# Voltage_Source.net
KiCad netlist of a schematic drawn in Altium Designer
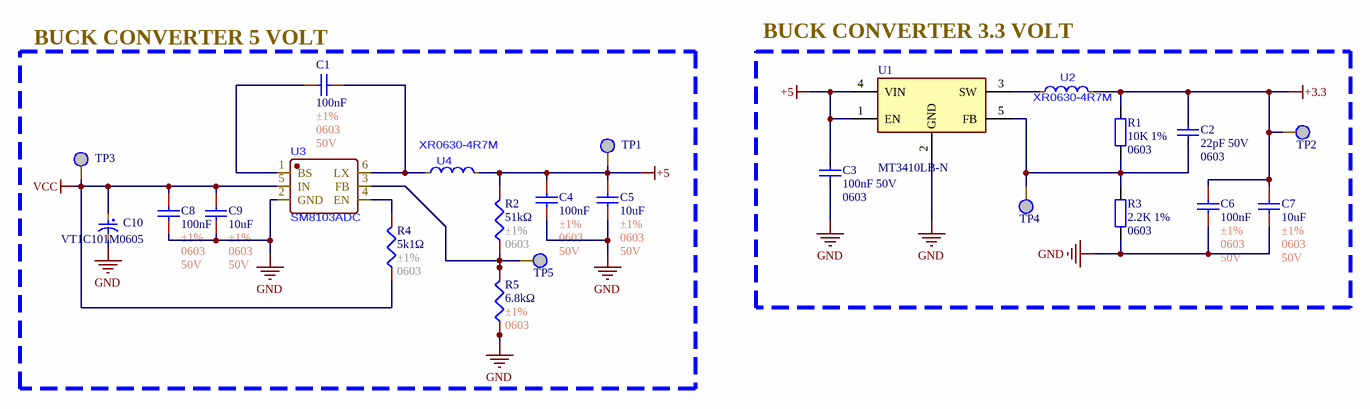
[diagram p0: Voltage Source.SchDoc]

(export (version "E")
  (design (tool "Eeschema 10.0.6"))
  (components
    (comp (ref "C1")
      (value "100nF")
      (footprint "C0603")
      (fields
        (field (name "MANUFACTURER") "YAGEO")
        (field (name "MFR. PART #") "CC0402FRNPO9BN100")
        (field (name "LCSC PART #") "C513681")
        (field (name "TOLERANCE") "±1%")
        (field (name "PACKAGE") "0603")
        (field (name "VOLTAGE RATING") "50V")
      )
      (libsource (lib "Capital") (part "C0603_100nF_±1%"))
    )
    (comp (ref "C2")
      (value "22pF 50V")
      (footprint "C0603")
      (description "50V 22pF NP0 ±5% 0603 Multilayer Ceramic Capacitors MLCC - SMD/SMT ROHS")
      (fields
        (field (name "MANUFACTURER") "YAGEO")
        (field (name "MANUFACTURE PART NUMBER") "CC0603JRNPO9BN220")
        (field (name "PACKAGE") "0603")
      )
      (libsource (lib "IOT SOLUTIONS LOAPAY V5.5.2") (part "C0603_MLCC_22pF_50V"))
    )
    (comp (ref "C3")
      (value "100nF 50V")
      (footprint "C0603")
      (description "50V 100nF X7R ±10% 0603 Multilayer Ceramic Capacitors MLCC - SMD/SMT ROHS")
      (fields
        (field (name "MANUFACTURER") "YAGEO")
        (field (name "MANUFACTURE PART NUMBER") "CC0603KRX7R9BB104")
        (field (name "PACKAGE") "0603")
      )
      (libsource (lib "IOT SOLUTIONS LOAPAY V5.5.2") (part "C0603_MLCC_100nF_50V"))
    )
    (comp (ref "C4")
      (value "100nF")
      (footprint "C0603")
      (fields
        (field (name "MANUFACTURER") "YAGEO")
        (field (name "MFR. PART #") "CC0402FRNPO9BN100")
        (field (name "LCSC PART #") "C513681")
        (field (name "TOLERANCE") "±1%")
        (field (name "PACKAGE") "0603")
        (field (name "VOLTAGE RATING") "50V")
      )
      (libsource (lib "Capital") (part "C0603_100nF_±1%"))
    )
    (comp (ref "C5")
      (value "10uF")
      (footprint "C0603")
      (fields
        (field (name "MANUFACTURER") "YAGEO")
        (field (name "MFR. PART #") "CC0402FRNPO9BN100")
        (field (name "LCSC PART #") "C513681")
        (field (name "TOLERANCE") "±1%")
        (field (name "PACKAGE") "0603")
        (field (name "VOLTAGE RATING") "50V")
      )
      (libsource (lib "Capital") (part "C0603_10uF_±1%"))
    )
    (comp (ref "C6")
      (value "100nF")
      (footprint "C0603")
      (fields
        (field (name "MANUFACTURER") "YAGEO")
        (field (name "MFR. PART #") "CC0402FRNPO9BN100")
        (field (name "LCSC PART #") "C513681")
        (field (name "TOLERANCE") "±1%")
        (field (name "PACKAGE") "0603")
        (field (name "VOLTAGE RATING") "50V")
      )
      (libsource (lib "Capital") (part "C0603_100nF_±1%"))
    )
    (comp (ref "C7")
      (value "10uF")
      (footprint "C0603")
      (fields
        (field (name "MANUFACTURER") "YAGEO")
        (field (name "MFR. PART #") "CC0402FRNPO9BN100")
        (field (name "LCSC PART #") "C513681")
        (field (name "TOLERANCE") "±1%")
        (field (name "PACKAGE") "0603")
        (field (name "VOLTAGE RATING") "50V")
      )
      (libsource (lib "Capital") (part "C0603_10uF_±1%"))
    )
    (comp (ref "C8")
      (value "100nF")
      (footprint "C0603")
      (fields
        (field (name "MANUFACTURER") "YAGEO")
        (field (name "MFR. PART #") "CC0402FRNPO9BN100")
        (field (name "LCSC PART #") "C513681")
        (field (name "TOLERANCE") "±1%")
        (field (name "PACKAGE") "0603")
        (field (name "VOLTAGE RATING") "50V")
      )
      (libsource (lib "Capital") (part "C0603_100nF_±1%"))
    )
    (comp (ref "C9")
      (value "10uF")
      (footprint "C0603")
      (fields
        (field (name "MANUFACTURER") "YAGEO")
        (field (name "MFR. PART #") "CC0402FRNPO9BN100")
        (field (name "LCSC PART #") "C513681")
        (field (name "TOLERANCE") "±1%")
        (field (name "PACKAGE") "0603")
        (field (name "VOLTAGE RATING") "50V")
      )
      (libsource (lib "Capital") (part "C0603_10uF_±1%"))
    )
    (comp (ref "C10")
      (value "VT1C101M0605")
      (footprint "C_100uF_16V_Aluminum")
      (description "100uF 16V ±20% 63mA@120Hz SMD,D6.3xL5.4mm Aluminum Electrolytic Capacitors RoHS")
      (fields (field (name "MANUFACTURER") "ROQANG") (field (name "LCSC PART #") "C90273"))
      (libsource (lib "Capital") (part "C_100uF_16V_aluminum"))
    )
    (comp (ref "R1")
      (value "10K 1%")
      (footprint "RES_SMD_0603")
      (description "10 kOhms ±1% 0.1W, 1/10W Chip Resistor 0603 (1608 Metric) Moisture Resistant Thick Film")
      (fields
        (field (name "MANUFACTURER") "YAGEO")
        (field (name "MANUFACTURE PART NUMBER") "RC0603FR-0710KL")
        (field (name "PACKAGE") "0603")
      )
      (libsource (lib "IOT SOLUTIONS LOAPAY V5.5.2") (part "R0603_10K"))
    )
    (comp (ref "R2")
      (value "51kΩ")
      (footprint "R0603")
      (description "100mW Thick Film Resistor 75V ±100ppm/℃ ±1% 51kΩ 0603 Chip Resistor - Surface Mount ROHS")
      (fields
        (field (name "MANUFACTURER") "FOJAN")
        (field (name "MFR. PART #") "FRC0603F5101TS")
        (field (name "TOLERANCE") "±1%")
        (field (name "PACKAGE") "0603")
      )
      (libsource (lib "Resistor") (part "R0603_51kΩ_±1%"))
    )
    (comp (ref "R3")
      (value "2.2K 1%")
      (footprint "RES_SMD_0603")
      (description "2.2 kOhms ±1% 0.1W, 1/10W Chip Resistor 0603 (1608 Metric) Moisture Resistant Thick Film")
      (fields
        (field (name "MANUFACTURER") "YAGEO")
        (field (name "MANUFACTURE PART NUMBER") "RC0603FR-072K2L")
        (field (name "PACKAGE") "0603")
      )
      (libsource (lib "IOT SOLUTIONS LOAPAY V5.5.2") (part "R0603_2.2K"))
    )
    (comp (ref "R4")
      (value "5k1Ω")
      (footprint "R0603")
      (description "100mW Thick Film Resistor 75V ±100ppm/℃ ±1% 5.1kΩ 0603 Chip Resistor - Surface Mount ROHS")
      (fields
        (field (name "MANUFACTURER") "FOJAN")
        (field (name "MFR. PART #") "FRC0603F5101TS")
        (field (name "TOLERANCE") "±1%")
        (field (name "PACKAGE") "0603")
      )
      (libsource (lib "Resistor") (part "R0603_5k1Ω_±1%"))
    )
    (comp (ref "R5")
      (value "6.8kΩ")
      (footprint "R0603")
      (description "6.8k")
      (fields
        (field (name "MANUFACTURER") "YAGEO")
        (field (name "MFR. PART #") "RC0402FR-0710RL")
        (field (name "TOLERANCE") "±1%")
        (field (name "PACKAGE") "0603")
      )
      (libsource (lib "Resistor") (part "R0603_6.8kΩ_±1%_1"))
    )
    (comp (ref "TP1") (value "TP") (footprint "TP") (libsource (lib "Other") (part "TP")))
    (comp (ref "TP2") (value "TP") (footprint "TP") (libsource (lib "Other") (part "TP")))
    (comp (ref "TP3") (value "TP") (footprint "TP") (libsource (lib "Other") (part "TP")))
    (comp (ref "TP4") (value "TP") (footprint "TP") (libsource (lib "Other") (part "TP")))
    (comp (ref "TP5") (value "TP") (footprint "TP") (libsource (lib "Other") (part "TP")))
    (comp (ref "U1")
      (value "MT3410LB-N")
      (footprint "SOT23_5")
      (description "SOT-23-5 DC-DC Converters ROHS")
      (fields (field (name "MANUFACTURER") "XI'AN Aerosemi Tech"))
      (libsource (lib "IOT SOLUTIONS LOAPAY V5.5.2") (part "MT3410LB-N"))
    )
    (comp (ref "U2")
      (value "XR0630-4R7M")
      (footprint "SMD,7x6.6mm")
      (description "FIXED IND 4.7uH 6A 33mΩ SMD,0630")
      (fields (field (name "MANUFACTURER") "XR") (field (name "LCSC PART #") "C5307631"))
      (libsource (lib "Inductor") (part "FIXED IND 4.7uH 6A 33mΩ SMD,0630"))
    )
    (comp (ref "U3")
      (value "SM8103ADC")
      (footprint "TSOT-23-6")
      (description "High Efficiency, 3.0A, 18V Input Synchronous Step Down Regulator")
      (fields (field (name "MANUFACTURER") "Silergy") (field (name "LCSC PART #") "C479070"))
      (libsource (lib "IC") (part "SM8103ADC"))
    )
    (comp (ref "U4")
      (value "XR0630-4R7M")
      (footprint "SMD,7x6.6mm")
      (description "FIXED IND 4.7uH 6A 33mΩ SMD,0630")
      (fields (field (name "MANUFACTURER") "XR") (field (name "LCSC PART #") "C5307631"))
      (libsource (lib "Inductor") (part "FIXED IND 4.7uH 6A 33mΩ SMD,0630"))
    )
  )
  (nets
    (net (code "1") (name "+3.3") (class "Default")
      (node (ref "C2") (pin "2") (pinfunction "2_2") (pintype "passive"))
      (node (ref "C6") (pin "1") (pinfunction "1_1") (pintype "passive"))
      (node (ref "C7") (pin "1") (pinfunction "1_1") (pintype "passive"))
      (node (ref "R1") (pin "2") (pinfunction "2_2") (pintype "passive"))
      (node (ref "TP2") (pin "1") (pinfunction "1_1") (pintype "passive"))
      (node (ref "U2") (pin "2") (pinfunction "F_2") (pintype "passive"))
    )
    (net (code "2") (name "+5") (class "Default")
      (node (ref "C3") (pin "2") (pinfunction "2_2") (pintype "passive"))
      (node (ref "C4") (pin "1") (pinfunction "1_1") (pintype "passive"))
      (node (ref "C5") (pin "1") (pinfunction "1_1") (pintype "passive"))
      (node (ref "R2") (pin "2") (pinfunction "2_2") (pintype "passive"))
      (node (ref "TP1") (pin "1") (pinfunction "1_1") (pintype "passive"))
      (node (ref "U1") (pin "1") (pinfunction "EN_1") (pintype "passive"))
      (node (ref "U1") (pin "4") (pinfunction "VIN_4") (pintype "passive"))
      (node (ref "U4") (pin "2") (pinfunction "F_2") (pintype "passive"))
    )
    (net (code "3") (name "GND") (class "Default")
      (node (ref "C10") (pin "2") (pinfunction "2_2") (pintype "passive"))
      (node (ref "C3") (pin "1") (pinfunction "1_1") (pintype "passive"))
      (node (ref "C4") (pin "2") (pinfunction "2_2") (pintype "passive"))
      (node (ref "C5") (pin "2") (pinfunction "2_2") (pintype "passive"))
      (node (ref "C6") (pin "2") (pinfunction "2_2") (pintype "passive"))
      (node (ref "C7") (pin "2") (pinfunction "2_2") (pintype "passive"))
      (node (ref "C8") (pin "2") (pinfunction "2_2") (pintype "passive"))
      (node (ref "C9") (pin "2") (pinfunction "2_2") (pintype "passive"))
      (node (ref "R3") (pin "1") (pinfunction "1_1") (pintype "passive"))
      (node (ref "R5") (pin "1") (pinfunction "1_1") (pintype "passive"))
      (node (ref "U1") (pin "2") (pinfunction "GND_2") (pintype "passive"))
      (node (ref "U3") (pin "2") (pinfunction "GND_2") (pintype "passive"))
    )
    (net (code "4") (name "Net-(U1-FB)") (class "Default")
      (node (ref "C2") (pin "1") (pinfunction "1_1") (pintype "passive"))
      (node (ref "R1") (pin "1") (pinfunction "1_1") (pintype "passive"))
      (node (ref "R3") (pin "2") (pinfunction "2_2") (pintype "passive"))
      (node (ref "TP4") (pin "1") (pinfunction "1_1") (pintype "passive"))
      (node (ref "U1") (pin "5") (pinfunction "FB_5") (pintype "passive"))
    )
    (net (code "5") (name "Net-(U1-SW)") (class "Default")
      (node (ref "U1") (pin "3") (pinfunction "SW_3") (pintype "passive"))
      (node (ref "U2") (pin "1") (pinfunction "S_1") (pintype "passive"))
    )
    (net (code "6") (name "Net-(U3-BS)") (class "Default")
      (node (ref "C1") (pin "2") (pinfunction "2_2") (pintype "passive"))
      (node (ref "U3") (pin "1") (pinfunction "BS_1") (pintype "passive"))
    )
    (net (code "7") (name "Net-(U3-EN)") (class "Default")
      (node (ref "R4") (pin "2") (pinfunction "2_2") (pintype "passive"))
      (node (ref "U3") (pin "4") (pinfunction "EN_4") (pintype "passive"))
    )
    (net (code "8") (name "Net-(U3-FB)") (class "Default")
      (node (ref "R2") (pin "1") (pinfunction "1_1") (pintype "passive"))
      (node (ref "R5") (pin "2") (pinfunction "2_2") (pintype "passive"))
      (node (ref "TP5") (pin "1") (pinfunction "1_1") (pintype "passive"))
      (node (ref "U3") (pin "3") (pinfunction "FB_3") (pintype "passive"))
    )
    (net (code "9") (name "Net-(U3-LX)") (class "Default")
      (node (ref "C1") (pin "1") (pinfunction "1_1") (pintype "passive"))
      (node (ref "U3") (pin "6") (pinfunction "LX_6") (pintype "passive"))
      (node (ref "U4") (pin "1") (pinfunction "S_1") (pintype "passive"))
    )
    (net (code "10") (name "VCC") (class "Default")
      (node (ref "C10") (pin "1") (pinfunction "1_1") (pintype "passive"))
      (node (ref "C8") (pin "1") (pinfunction "1_1") (pintype "passive"))
      (node (ref "C9") (pin "1") (pinfunction "1_1") (pintype "passive"))
      (node (ref "R4") (pin "1") (pinfunction "1_1") (pintype "passive"))
      (node (ref "TP3") (pin "1") (pinfunction "1_1") (pintype "passive"))
      (node (ref "U3") (pin "5") (pinfunction "IN_5") (pintype "passive"))
    )
  )
)
